# HoneyBee.net
KiCad netlist of a schematic drawn in EAGLE
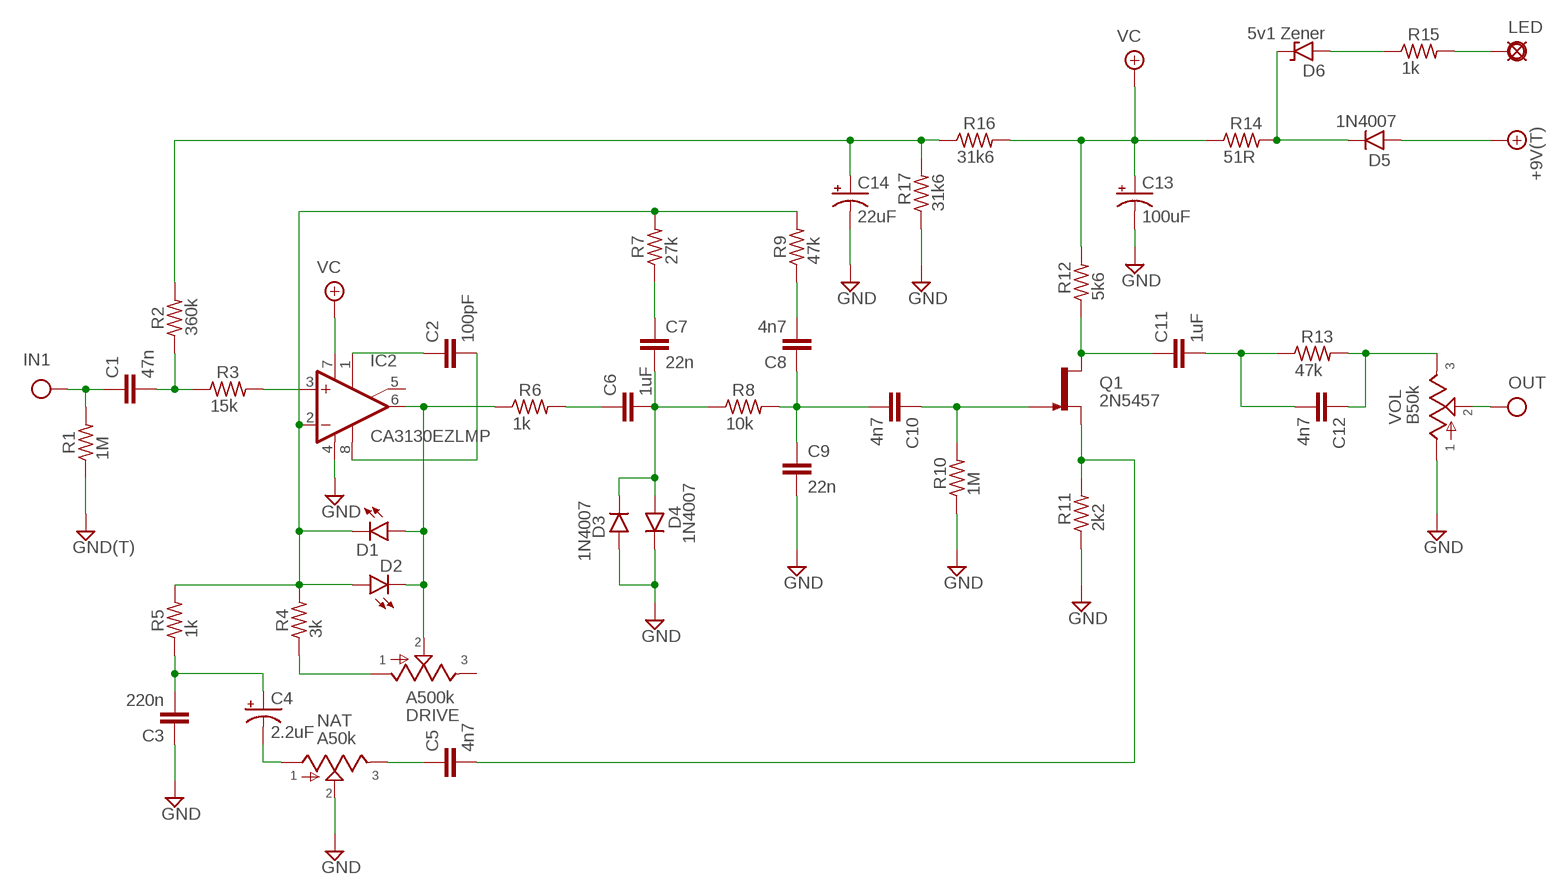
[diagram p0: schematic, sheet 1]

(export (version "E")
  (design (tool "Eeschema 10.0.6"))
  (components
    (comp (ref "+9V")
      (value "+9V(T)")
      (footprint "eagle-import:SQUARE")
      (libsource (lib "eagle-import") (part "+9V(T)"))
    )
    (comp (ref "C1")
      (value "47n")
      (footprint "eagle-import:075X040")
      (libsource (lib "eagle-import") (part "075X0402"))
    )
    (comp (ref "C2")
      (value "100pF")
      (footprint "eagle-import:050X030_025")
      (libsource (lib "eagle-import") (part "050X030_0251"))
    )
    (comp (ref "C3")
      (value "220n")
      (footprint "eagle-import:080X050")
      (libsource (lib "eagle-import") (part "080X0502"))
    )
    (comp (ref "C4")
      (value "2.2uF")
      (footprint "eagle-import:050_020_1")
      (libsource (lib "eagle-import") (part "0501"))
    )
    (comp (ref "C5")
      (value "4n7")
      (footprint "eagle-import:070X030")
      (libsource (lib "eagle-import") (part "070X0302"))
    )
    (comp (ref "C6")
      (value "1uF")
      (footprint "eagle-import:080X050")
      (libsource (lib "eagle-import") (part "080X0502"))
    )
    (comp (ref "C7")
      (value "22n")
      (footprint "eagle-import:075X030")
      (libsource (lib "eagle-import") (part "075X0302"))
    )
    (comp (ref "C8")
      (value "4n7")
      (footprint "eagle-import:070X030")
      (libsource (lib "eagle-import") (part "070X0302"))
    )
    (comp (ref "C9")
      (value "22n")
      (footprint "eagle-import:075X030")
      (libsource (lib "eagle-import") (part "075X0302"))
    )
    (comp (ref "C10")
      (value "4n7")
      (footprint "eagle-import:070X030")
      (libsource (lib "eagle-import") (part "070X0302"))
    )
    (comp (ref "C11")
      (value "1uF")
      (footprint "eagle-import:080X050")
      (libsource (lib "eagle-import") (part "080X0502"))
    )
    (comp (ref "C12")
      (value "4n7")
      (footprint "eagle-import:070X030")
      (libsource (lib "eagle-import") (part "070X0302"))
    )
    (comp (ref "C13")
      (value "100uF")
      (footprint "eagle-import:080_035_1")
      (libsource (lib "eagle-import") (part "0801"))
    )
    (comp (ref "C14")
      (value "22uF")
      (footprint "eagle-import:050_020_1")
      (libsource (lib "eagle-import") (part "0501"))
    )
    (comp (ref "D1")
      (value "LED3MM")
      (footprint "eagle-import:LED3MM")
      (libsource (lib "eagle-import") (part "LED3MM"))
    )
    (comp (ref "D2")
      (value "LED3MM")
      (footprint "eagle-import:LED3MM")
      (libsource (lib "eagle-import") (part "LED3MM"))
    )
    (comp (ref "D3")
      (value "1N4007")
      (footprint "eagle-import:DO41-3")
      (libsource (lib "eagle-import") (part "1N400X.3"))
    )
    (comp (ref "D4")
      (value "1N4007")
      (footprint "eagle-import:DO41-3")
      (libsource (lib "eagle-import") (part "1N400X.3"))
    )
    (comp (ref "D5")
      (value "1N4007")
      (footprint "eagle-import:DO41-3")
      (libsource (lib "eagle-import") (part "1N400X.3"))
    )
    (comp (ref "D6")
      (value "5v1 Zener")
      (footprint "eagle-import:DO35-3")
      (libsource (lib "eagle-import") (part "1N9ZENER"))
    )
    (comp (ref "DRIVE")
      (value "A500k")
      (footprint "eagle-import:POT")
      (libsource (lib "eagle-import") (part "POT"))
    )
    (comp (ref "G1")
      (value "GND(T)")
      (footprint "eagle-import:SQUARE")
      (libsource (lib "eagle-import") (part "GND(T)"))
    )
    (comp (ref "IC2")
      (value "CA3130EZLMP")
      (footprint "eagle-import:DIL08")
      (libsource (lib "eagle-import") (part "CA3130EZPLM"))
    )
    (comp (ref "IN1")
      (value "IN(T)")
      (footprint "eagle-import:SQUARE")
      (libsource (lib "eagle-import") (part "IN(T)"))
    )
    (comp (ref "LED")
      (value "3mm")
      (footprint "eagle-import:SQUARE")
      (libsource (lib "eagle-import") (part "PAD"))
    )
    (comp (ref "NAT")
      (value "A50k")
      (footprint "eagle-import:POT")
      (libsource (lib "eagle-import") (part "POT"))
    )
    (comp (ref "OUT")
      (value "OUT(T)")
      (footprint "eagle-import:SQUARE")
      (libsource (lib "eagle-import") (part "OUT(T)"))
    )
    (comp (ref "Q1")
      (value "2N5457")
      (footprint "eagle-import:TO92-")
      (libsource (lib "eagle-import") (part "2N5457"))
    )
    (comp (ref "R1")
      (value "1M")
      (footprint "eagle-import:R0207_3")
      (libsource (lib "eagle-import") (part "6MM.3"))
    )
    (comp (ref "R2")
      (value "360k")
      (footprint "eagle-import:R0207_3")
      (libsource (lib "eagle-import") (part "6MM.3"))
    )
    (comp (ref "R3")
      (value "15k")
      (footprint "eagle-import:R0207_3")
      (libsource (lib "eagle-import") (part "6MM.3"))
    )
    (comp (ref "R4")
      (value "3k")
      (footprint "eagle-import:R0207_3")
      (libsource (lib "eagle-import") (part "6MM.3"))
    )
    (comp (ref "R5")
      (value "1k")
      (footprint "eagle-import:R0207_3")
      (libsource (lib "eagle-import") (part "6MM.3"))
    )
    (comp (ref "R6")
      (value "1k")
      (footprint "eagle-import:R0207_3")
      (libsource (lib "eagle-import") (part "6MM.3"))
    )
    (comp (ref "R7")
      (value "27k")
      (footprint "eagle-import:R0207_3")
      (libsource (lib "eagle-import") (part "6MM.3"))
    )
    (comp (ref "R8")
      (value "10k")
      (footprint "eagle-import:R0207_3")
      (libsource (lib "eagle-import") (part "6MM.3"))
    )
    (comp (ref "R9")
      (value "47k")
      (footprint "eagle-import:R0207_3")
      (libsource (lib "eagle-import") (part "6MM.3"))
    )
    (comp (ref "R10")
      (value "1M")
      (footprint "eagle-import:R0207_3")
      (libsource (lib "eagle-import") (part "6MM.3"))
    )
    (comp (ref "R11")
      (value "2k2")
      (footprint "eagle-import:R0207_3")
      (libsource (lib "eagle-import") (part "6MM.3"))
    )
    (comp (ref "R12")
      (value "5k6")
      (footprint "eagle-import:R0207_3")
      (libsource (lib "eagle-import") (part "6MM.3"))
    )
    (comp (ref "R13")
      (value "47k")
      (footprint "eagle-import:R0207_3")
      (libsource (lib "eagle-import") (part "6MM.3"))
    )
    (comp (ref "R14")
      (value "51R")
      (footprint "eagle-import:R0207_3")
      (libsource (lib "eagle-import") (part "6MM.3"))
    )
    (comp (ref "R15")
      (value "1k")
      (footprint "eagle-import:R0207_3")
      (libsource (lib "eagle-import") (part "6MM.3"))
    )
    (comp (ref "R16")
      (value "31k6")
      (footprint "eagle-import:R0207_3")
      (libsource (lib "eagle-import") (part "6MM.3"))
    )
    (comp (ref "R17")
      (value "31k6")
      (footprint "eagle-import:R0207_3")
      (libsource (lib "eagle-import") (part "6MM.3"))
    )
    (comp (ref "VOL")
      (value "B50k")
      (footprint "eagle-import:POT")
      (libsource (lib "eagle-import") (part "POT"))
    )
  )
  (nets
    (net (code "1") (name "+9V(T)") (class "Default")
      (node (ref "+9V") (pin "1") (pinfunction "+9V_1") (pintype "power_in"))
      (node (ref "D5") (pin "A") (pinfunction "A_A") (pintype "passive"))
    )
    (net (code "2") (name "GND") (class "Default")
      (node (ref "C13") (pin "-") (pinfunction "-_-") (pintype "passive"))
      (node (ref "C14") (pin "-") (pinfunction "-_-") (pintype "passive"))
      (node (ref "C3") (pin "1") (pinfunction "1_1") (pintype "passive"))
      (node (ref "C9") (pin "2") (pinfunction "2_2") (pintype "passive"))
      (node (ref "D3") (pin "A") (pinfunction "A_A") (pintype "passive"))
      (node (ref "D4") (pin "C") (pinfunction "C_C") (pintype "passive"))
      (node (ref "G1") (pin "1") (pinfunction "GND_1") (pintype "power_in"))
      (node (ref "IC2") (pin "4") (pinfunction "V-_4") (pintype "power_in"))
      (node (ref "NAT") (pin "2") (pinfunction "2_2") (pintype "passive"))
      (node (ref "R1") (pin "1") (pinfunction "1_1") (pintype "passive"))
      (node (ref "R10") (pin "1") (pinfunction "1_1") (pintype "passive"))
      (node (ref "R11") (pin "1") (pinfunction "1_1") (pintype "passive"))
      (node (ref "R17") (pin "1") (pinfunction "1_1") (pintype "passive"))
      (node (ref "VOL") (pin "1") (pinfunction "1_1") (pintype "passive"))
    )
    (net (code "3") (name "IN(T)") (class "Default")
      (node (ref "C1") (pin "1") (pinfunction "1_1") (pintype "passive"))
      (node (ref "IN1") (pin "1") (pinfunction "IN_1") (pintype "power_in"))
      (node (ref "R1") (pin "2") (pinfunction "2_2") (pintype "passive"))
    )
    (net (code "4") (name "Net-(C1-Pad2)") (class "Default")
      (node (ref "C1") (pin "2") (pinfunction "2_2") (pintype "passive"))
      (node (ref "R2") (pin "1") (pinfunction "1_1") (pintype "passive"))
      (node (ref "R3") (pin "1") (pinfunction "1_1") (pintype "passive"))
    )
    (net (code "5") (name "Net-(C3-Pad2)") (class "Default")
      (node (ref "C3") (pin "2") (pinfunction "2_2") (pintype "passive"))
      (node (ref "C4") (pin "+") (pinfunction "+_+") (pintype "passive"))
      (node (ref "R5") (pin "1") (pinfunction "1_1") (pintype "passive"))
    )
    (net (code "6") (name "Net-(C4-Pad-)") (class "Default")
      (node (ref "C4") (pin "-") (pinfunction "-_-") (pintype "passive"))
      (node (ref "NAT") (pin "1") (pinfunction "1_1") (pintype "passive"))
    )
    (net (code "7") (name "Net-(C5-Pad1)") (class "Default")
      (node (ref "C5") (pin "1") (pinfunction "1_1") (pintype "passive"))
      (node (ref "NAT") (pin "3") (pinfunction "3_3") (pintype "passive"))
    )
    (net (code "8") (name "Net-(C6-Pad1)") (class "Default")
      (node (ref "C6") (pin "1") (pinfunction "1_1") (pintype "passive"))
      (node (ref "R6") (pin "2") (pinfunction "2_2") (pintype "passive"))
    )
    (net (code "9") (name "Net-(C6-Pad2)") (class "Default")
      (node (ref "C6") (pin "2") (pinfunction "2_2") (pintype "passive"))
      (node (ref "C7") (pin "2") (pinfunction "2_2") (pintype "passive"))
      (node (ref "D3") (pin "C") (pinfunction "C_C") (pintype "passive"))
      (node (ref "D4") (pin "A") (pinfunction "A_A") (pintype "passive"))
      (node (ref "R8") (pin "1") (pinfunction "1_1") (pintype "passive"))
    )
    (net (code "10") (name "Net-(C7-Pad1)") (class "Default")
      (node (ref "C7") (pin "1") (pinfunction "1_1") (pintype "passive"))
      (node (ref "R7") (pin "1") (pinfunction "1_1") (pintype "passive"))
    )
    (net (code "11") (name "Net-(C8-Pad2)") (class "Default")
      (node (ref "C8") (pin "2") (pinfunction "2_2") (pintype "passive"))
      (node (ref "R9") (pin "1") (pinfunction "1_1") (pintype "passive"))
    )
    (net (code "12") (name "Net-(C10-Pad2)") (class "Default")
      (node (ref "C10") (pin "2") (pinfunction "2_2") (pintype "passive"))
      (node (ref "C8") (pin "1") (pinfunction "1_1") (pintype "passive"))
      (node (ref "C9") (pin "1") (pinfunction "1_1") (pintype "passive"))
      (node (ref "R8") (pin "2") (pinfunction "2_2") (pintype "passive"))
    )
    (net (code "13") (name "Net-(C11-Pad2)") (class "Default")
      (node (ref "C11") (pin "2") (pinfunction "2_2") (pintype "passive"))
      (node (ref "C12") (pin "2") (pinfunction "2_2") (pintype "passive"))
      (node (ref "R13") (pin "1") (pinfunction "1_1") (pintype "passive"))
    )
    (net (code "14") (name "Net-(C12-Pad1)") (class "Default")
      (node (ref "C12") (pin "1") (pinfunction "1_1") (pintype "passive"))
      (node (ref "R13") (pin "2") (pinfunction "2_2") (pintype "passive"))
      (node (ref "VOL") (pin "3") (pinfunction "3_3") (pintype "passive"))
    )
    (net (code "15") (name "Net-(C14-Pad+)") (class "Default")
      (node (ref "C14") (pin "+") (pinfunction "+_+") (pintype "passive"))
      (node (ref "R16") (pin "1") (pinfunction "1_1") (pintype "passive"))
      (node (ref "R17") (pin "2") (pinfunction "2_2") (pintype "passive"))
      (node (ref "R2") (pin "2") (pinfunction "2_2") (pintype "passive"))
    )
    (net (code "16") (name "Net-(D1-C)") (class "Default")
      (node (ref "D1") (pin "K") (pinfunction "C_K") (pintype "passive"))
      (node (ref "D2") (pin "A") (pinfunction "A_A") (pintype "passive"))
      (node (ref "IC2") (pin "2") (pinfunction "-IN_2") (pintype "input"))
      (node (ref "R4") (pin "2") (pinfunction "2_2") (pintype "passive"))
      (node (ref "R5") (pin "2") (pinfunction "2_2") (pintype "passive"))
      (node (ref "R7") (pin "2") (pinfunction "2_2") (pintype "passive"))
      (node (ref "R9") (pin "2") (pinfunction "2_2") (pintype "passive"))
    )
    (net (code "17") (name "Net-(D2-C)") (class "Default")
      (node (ref "D1") (pin "A") (pinfunction "A_A") (pintype "passive"))
      (node (ref "D2") (pin "K") (pinfunction "C_K") (pintype "passive"))
      (node (ref "DRIVE") (pin "2") (pinfunction "2_2") (pintype "passive"))
      (node (ref "IC2") (pin "6") (pinfunction "OUT_6") (pintype "output"))
      (node (ref "R6") (pin "1") (pinfunction "1_1") (pintype "passive"))
    )
    (net (code "18") (name "Net-(D5-PadC)") (class "Default")
      (node (ref "D5") (pin "C") (pinfunction "C_C") (pintype "passive"))
      (node (ref "D6") (pin "C") (pinfunction "C_C") (pintype "passive"))
      (node (ref "R14") (pin "2") (pinfunction "2_2") (pintype "passive"))
    )
    (net (code "19") (name "Net-(D6-PadA)") (class "Default")
      (node (ref "D6") (pin "A") (pinfunction "A_A") (pintype "passive"))
      (node (ref "R15") (pin "1") (pinfunction "1_1") (pintype "passive"))
    )
    (net (code "20") (name "Net-(DRIVE-Pad1)") (class "Default")
      (node (ref "DRIVE") (pin "1") (pinfunction "1_1") (pintype "passive"))
      (node (ref "R4") (pin "1") (pinfunction "1_1") (pintype "passive"))
    )
    (net (code "21") (name "Net-(IC2-+IN)") (class "Default")
      (node (ref "IC2") (pin "3") (pinfunction "+IN_3") (pintype "input"))
      (node (ref "R3") (pin "2") (pinfunction "2_2") (pintype "passive"))
    )
    (net (code "22") (name "Net-(IC2-ON1)") (class "Default")
      (node (ref "C2") (pin "1") (pinfunction "1_1") (pintype "passive"))
      (node (ref "IC2") (pin "1") (pinfunction "ON1_1") (pintype "passive"))
    )
    (net (code "23") (name "Net-(IC2-OPT)") (class "Default")
      (node (ref "C2") (pin "2") (pinfunction "2_2") (pintype "passive"))
      (node (ref "IC2") (pin "8") (pinfunction "OPT_8") (pintype "passive"))
    )
    (net (code "24") (name "Net-(LED-PAD)") (class "Default")
      (node (ref "LED") (pin "1") (pinfunction "PAD_1") (pintype "passive"))
      (node (ref "R15") (pin "2") (pinfunction "2_2") (pintype "passive"))
    )
    (net (code "25") (name "Net-(Q1-D)") (class "Default")
      (node (ref "C11") (pin "1") (pinfunction "1_1") (pintype "passive"))
      (node (ref "Q1") (pin "3") (pinfunction "D_3") (pintype "passive"))
      (node (ref "R12") (pin "1") (pinfunction "1_1") (pintype "passive"))
    )
    (net (code "26") (name "Net-(Q1-G)") (class "Default")
      (node (ref "C10") (pin "1") (pinfunction "1_1") (pintype "passive"))
      (node (ref "Q1") (pin "1") (pinfunction "G_1") (pintype "passive"))
      (node (ref "R10") (pin "2") (pinfunction "2_2") (pintype "passive"))
    )
    (net (code "27") (name "Net-(Q1-S)") (class "Default")
      (node (ref "C5") (pin "2") (pinfunction "2_2") (pintype "passive"))
      (node (ref "Q1") (pin "2") (pinfunction "S_2") (pintype "passive"))
      (node (ref "R11") (pin "2") (pinfunction "2_2") (pintype "passive"))
    )
    (net (code "28") (name "OUT(T)") (class "Default")
      (node (ref "OUT") (pin "1") (pinfunction "OUT_1") (pintype "power_in"))
      (node (ref "VOL") (pin "2") (pinfunction "2_2") (pintype "passive"))
    )
    (net (code "29") (name "VC") (class "Default")
      (node (ref "C13") (pin "+") (pinfunction "+_+") (pintype "passive"))
      (node (ref "IC2") (pin "7") (pinfunction "V+_7") (pintype "power_in"))
      (node (ref "R12") (pin "2") (pinfunction "2_2") (pintype "passive"))
      (node (ref "R14") (pin "1") (pinfunction "1_1") (pintype "passive"))
      (node (ref "R16") (pin "2") (pinfunction "2_2") (pintype "passive"))
    )
    (net (code "30") (name "unconnected-(DRIVE-Pad3)") (class "Default")
      (node (ref "DRIVE") (pin "3") (pinfunction "3_3") (pintype "passive"))
    )
    (net (code "31") (name "unconnected-(IC2-ON2-Pad5)") (class "Default")
      (node (ref "IC2") (pin "5") (pinfunction "ON2_5") (pintype "passive"))
    )
  )
)
